# RGBI2Cv2.net
KiCad netlist of a schematic drawn in EAGLE
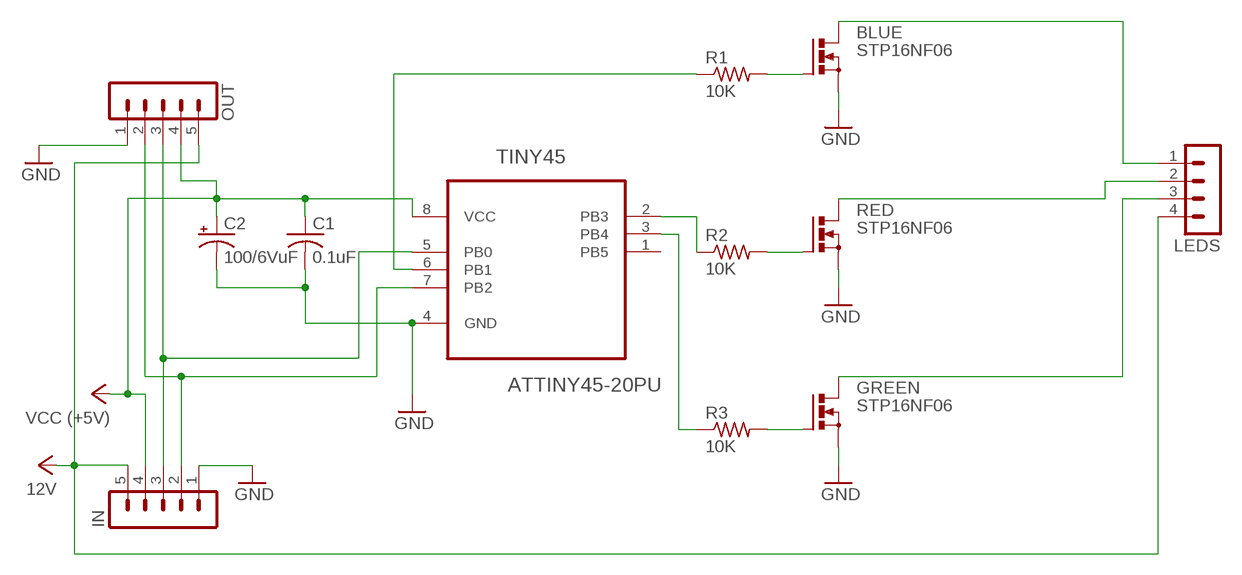
[diagram p0: schematic, sheet 1]

(export (version "E")
  (design (tool "Eeschema 10.0.6"))
  (components
    (comp (ref "BLUE")
      (value "STP16NF06")
      (footprint "eagle-import:TO220BH")
      (libsource (lib "eagle-import") (part "PMOSFET_NTO220BH"))
    )
    (comp (ref "C1")
      (value "0.1uF")
      (footprint "eagle-import:C025-025X050")
      (libsource (lib "eagle-import") (part "C-US025-025X050"))
    )
    (comp (ref "C2")
      (value "100/6VuF")
      (footprint "eagle-import:E2,5-6")
      (libsource (lib "eagle-import") (part "CPOL-USE2.5-6"))
    )
    (comp (ref "GREEN")
      (value "STP16NF06")
      (footprint "eagle-import:TO220BH")
      (libsource (lib "eagle-import") (part "PMOSFET_NTO220BH"))
    )
    (comp (ref "IN")
      (value "MA05-1")
      (footprint "eagle-import:MA05-1")
      (libsource (lib "eagle-import") (part "MA05-1"))
    )
    (comp (ref "LEDS")
      (value "MA04-1")
      (footprint "eagle-import:MA04-1")
      (libsource (lib "eagle-import") (part "MA04-1"))
    )
    (comp (ref "OUT")
      (value "MA05-1")
      (footprint "eagle-import:MA05-1")
      (libsource (lib "eagle-import") (part "MA05-1"))
    )
    (comp (ref "R1")
      (value "10K")
      (footprint "eagle-import:0207_7")
      (libsource (lib "eagle-import") (part "R-US_0207/7"))
    )
    (comp (ref "R2")
      (value "10K")
      (footprint "eagle-import:0207_7")
      (libsource (lib "eagle-import") (part "R-US_0207/7"))
    )
    (comp (ref "R3")
      (value "10K")
      (footprint "eagle-import:0207_7")
      (libsource (lib "eagle-import") (part "R-US_0207/7"))
    )
    (comp (ref "RED")
      (value "STP16NF06")
      (footprint "eagle-import:TO220BH")
      (libsource (lib "eagle-import") (part "PMOSFET_NTO220BH"))
    )
    (comp (ref "TINY45")
      (value "ATTINY45-20PU")
      (footprint "eagle-import:DIP254P762X533-8")
      (libsource (lib "eagle-import") (part "ATTINY45-20PU"))
    )
  )
  (nets
    (net (code "1") (name "12V") (class "Default")
      (node (ref "IN") (pin "5") (pinfunction "5_5") (pintype "passive"))
      (node (ref "LEDS") (pin "4") (pinfunction "4_4") (pintype "passive"))
      (node (ref "OUT") (pin "5") (pinfunction "5_5") (pintype "passive"))
    )
    (net (code "2") (name "GND") (class "Default")
      (node (ref "BLUE") (pin "S") (pinfunction "S_S") (pintype "passive"))
      (node (ref "C1") (pin "2") (pinfunction "2_2") (pintype "passive"))
      (node (ref "C2") (pin "-") (pinfunction "-_-") (pintype "passive"))
      (node (ref "GREEN") (pin "S") (pinfunction "S_S") (pintype "passive"))
      (node (ref "IN") (pin "1") (pinfunction "1_1") (pintype "passive"))
      (node (ref "OUT") (pin "1") (pinfunction "1_1") (pintype "passive"))
      (node (ref "RED") (pin "S") (pinfunction "S_S") (pintype "passive"))
      (node (ref "TINY45") (pin "4") (pinfunction "GND_4") (pintype "passive"))
    )
    (net (code "3") (name "Net-(BLUE-PadD)") (class "Default")
      (node (ref "BLUE") (pin "D") (pinfunction "D_D") (pintype "passive"))
      (node (ref "LEDS") (pin "1") (pinfunction "1_1") (pintype "passive"))
    )
    (net (code "4") (name "Net-(BLUE-PadG)") (class "Default")
      (node (ref "BLUE") (pin "G") (pinfunction "G_G") (pintype "passive"))
      (node (ref "R1") (pin "2") (pinfunction "2_2") (pintype "passive"))
    )
    (net (code "5") (name "Net-(GREEN-PadD)") (class "Default")
      (node (ref "GREEN") (pin "D") (pinfunction "D_D") (pintype "passive"))
      (node (ref "LEDS") (pin "3") (pinfunction "3_3") (pintype "passive"))
    )
    (net (code "6") (name "Net-(GREEN-PadG)") (class "Default")
      (node (ref "GREEN") (pin "G") (pinfunction "G_G") (pintype "passive"))
      (node (ref "R3") (pin "2") (pinfunction "2_2") (pintype "passive"))
    )
    (net (code "7") (name "Net-(LEDS-Pad2)") (class "Default")
      (node (ref "LEDS") (pin "2") (pinfunction "2_2") (pintype "passive"))
      (node (ref "RED") (pin "D") (pinfunction "D_D") (pintype "passive"))
    )
    (net (code "8") (name "Net-(R2-Pad2)") (class "Default")
      (node (ref "R2") (pin "2") (pinfunction "2_2") (pintype "passive"))
      (node (ref "RED") (pin "G") (pinfunction "G_G") (pintype "passive"))
    )
    (net (code "9") (name "Net-(TINY45-PB0)") (class "Default")
      (node (ref "IN") (pin "3") (pinfunction "3_3") (pintype "passive"))
      (node (ref "OUT") (pin "3") (pinfunction "3_3") (pintype "passive"))
      (node (ref "TINY45") (pin "5") (pinfunction "PB0_5") (pintype "bidirectional"))
    )
    (net (code "10") (name "Net-(TINY45-PB1)") (class "Default")
      (node (ref "R1") (pin "1") (pinfunction "1_1") (pintype "passive"))
      (node (ref "TINY45") (pin "6") (pinfunction "PB1_6") (pintype "bidirectional"))
    )
    (net (code "11") (name "Net-(TINY45-PB2)") (class "Default")
      (node (ref "IN") (pin "2") (pinfunction "2_2") (pintype "passive"))
      (node (ref "OUT") (pin "2") (pinfunction "2_2") (pintype "passive"))
      (node (ref "TINY45") (pin "7") (pinfunction "PB2_7") (pintype "bidirectional"))
    )
    (net (code "12") (name "Net-(TINY45-PB3)") (class "Default")
      (node (ref "R2") (pin "1") (pinfunction "1_1") (pintype "passive"))
      (node (ref "TINY45") (pin "2") (pinfunction "PB3_2") (pintype "bidirectional"))
    )
    (net (code "13") (name "Net-(TINY45-PB4)") (class "Default")
      (node (ref "R3") (pin "1") (pinfunction "1_1") (pintype "passive"))
      (node (ref "TINY45") (pin "3") (pinfunction "PB4_3") (pintype "bidirectional"))
    )
    (net (code "14") (name "VCC (+5V)") (class "Default")
      (node (ref "C1") (pin "1") (pinfunction "1_1") (pintype "passive"))
      (node (ref "C2") (pin "+") (pinfunction "+_+") (pintype "passive"))
      (node (ref "IN") (pin "4") (pinfunction "4_4") (pintype "passive"))
      (node (ref "OUT") (pin "4") (pinfunction "4_4") (pintype "passive"))
      (node (ref "TINY45") (pin "8") (pinfunction "VCC_8") (pintype "power_in"))
    )
    (net (code "15") (name "unconnected-(TINY45-PB5-Pad1)") (class "Default")
      (node (ref "TINY45") (pin "1") (pinfunction "PB5_1") (pintype "bidirectional"))
    )
  )
)
